# 7segement4digits1badidea-mk-4_1-smd.net
KiCad netlist of a schematic drawn in EAGLE
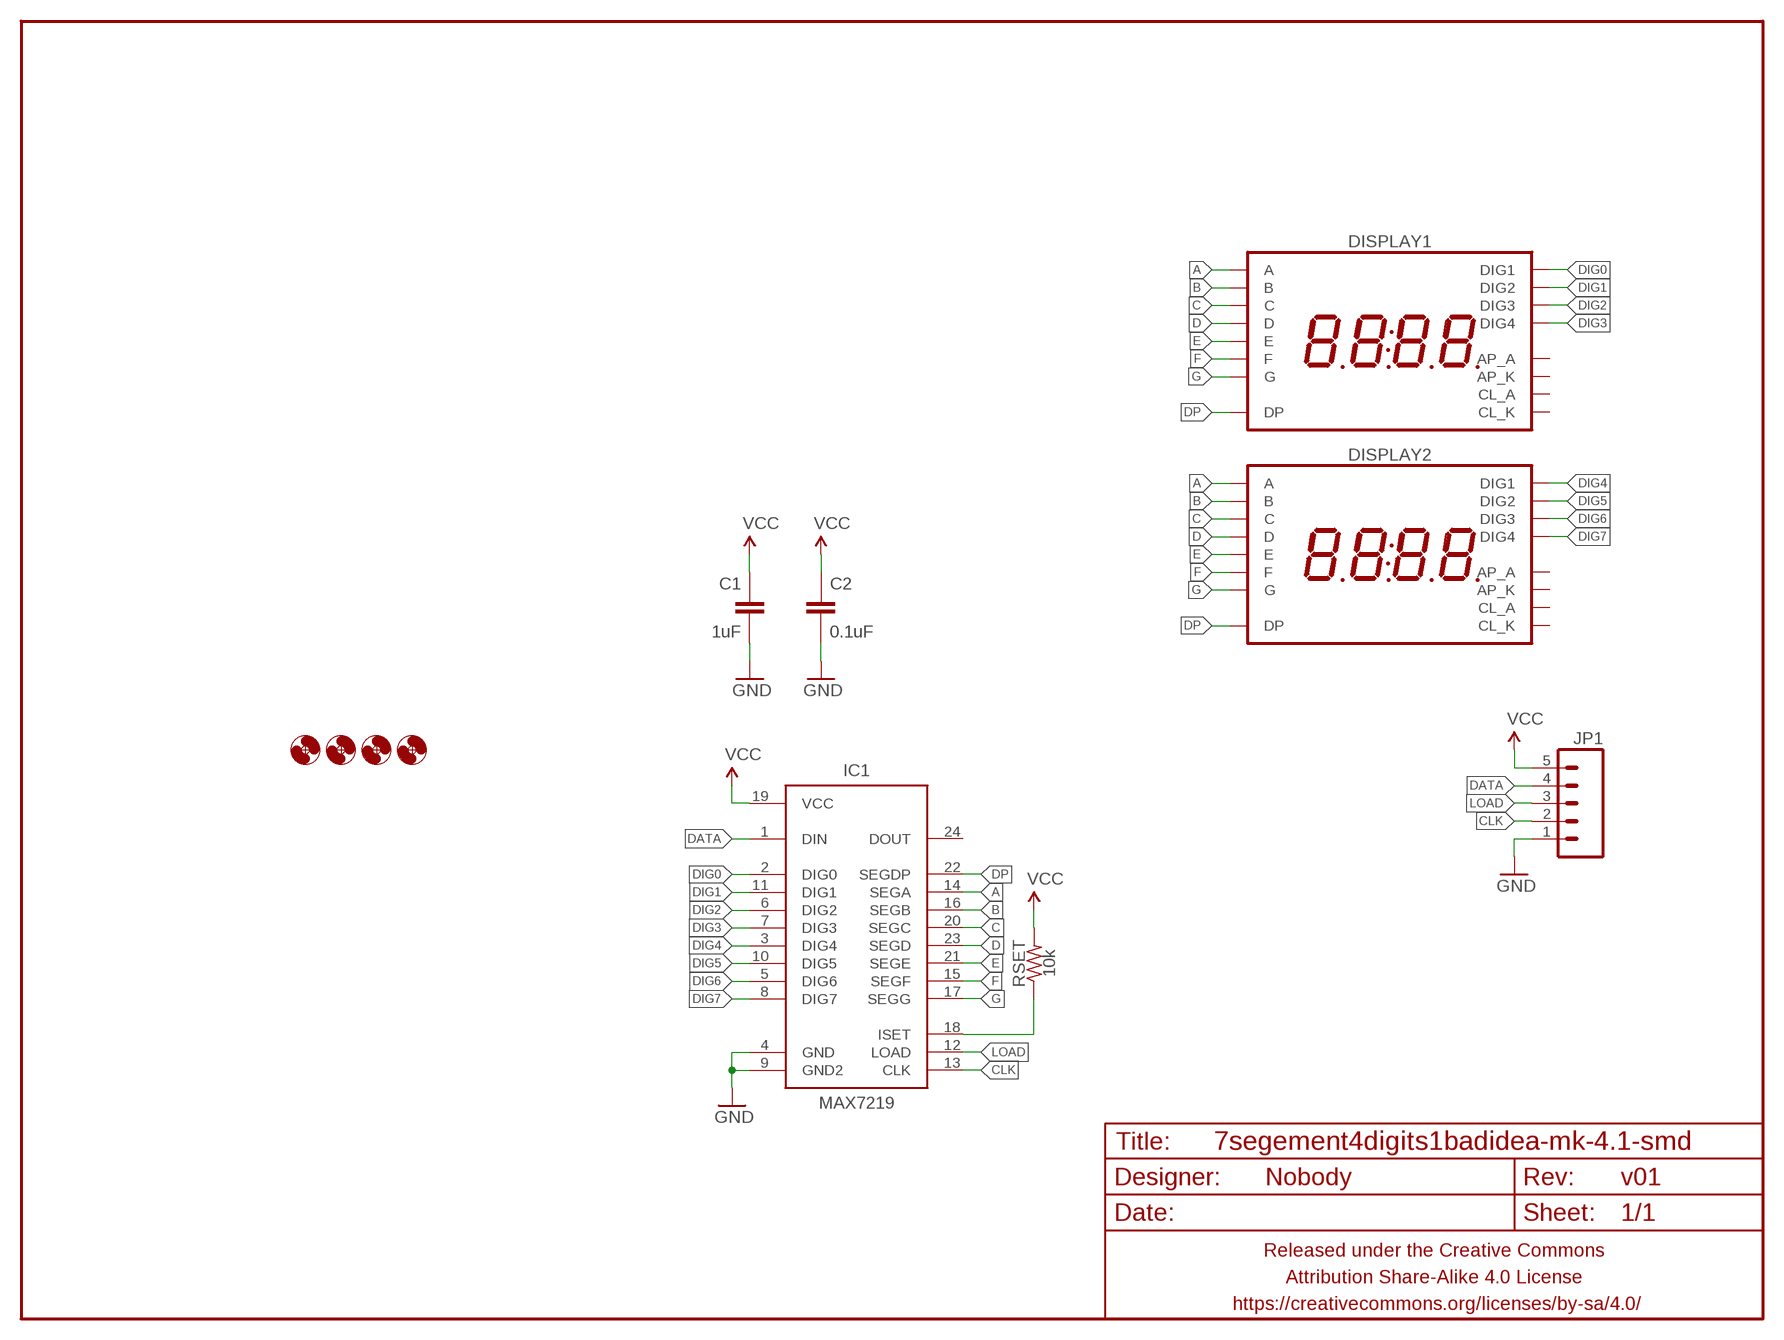
[diagram p0: schematic, sheet 1]

(export (version "E")
  (design (tool "Eeschema 10.0.6"))
  (components
    (comp (ref "C1")
      (value "1uF")
      (footprint "eagle-import:C025-024X044")
      (libsource (lib "eagle-import") (part "CAPACITOR-CERAMIC025-024X044"))
    )
    (comp (ref "C2")
      (value "0.1uF")
      (footprint "eagle-import:C025-024X044")
      (libsource (lib "eagle-import") (part "CAPACITOR-CERAMIC025-024X044"))
    )
    (comp (ref "DISPLAY1")
      (value "7SEG_4DIGIT_COLON_APOS")
      (footprint "eagle-import:7SEG_4DIG_10MM")
      (libsource (lib "eagle-import") (part "7SEG_4DIGIT_COLON_APOS"))
    )
    (comp (ref "DISPLAY2")
      (value "7SEG_4DIGIT_COLON_APOS")
      (footprint "eagle-import:7SEG_4DIG_10MM")
      (libsource (lib "eagle-import") (part "7SEG_4DIGIT_COLON_APOS"))
    )
    (comp (ref "FRAME1")
      (value "FRAME-LETTERNO_PACKAGE")
      (footprint "eagle-import:DUMMY")
      (fields (field (name "DESIGNER") "Nobody"))
      (libsource (lib "eagle-import") (part "FRAME-LETTERNO_PACKAGE"))
    )
    (comp (ref "H1")
      (value "HOLE#2")
      (footprint "eagle-import:HOLE-#2")
      (libsource (lib "eagle-import") (part "HOLE#2"))
    )
    (comp (ref "H2")
      (value "HOLE#2")
      (footprint "eagle-import:HOLE-#2")
      (libsource (lib "eagle-import") (part "HOLE#2"))
    )
    (comp (ref "H3")
      (value "HOLE#2")
      (footprint "eagle-import:HOLE-#2")
      (libsource (lib "eagle-import") (part "HOLE#2"))
    )
    (comp (ref "H4")
      (value "HOLE#2")
      (footprint "eagle-import:HOLE-#2")
      (libsource (lib "eagle-import") (part "HOLE#2"))
    )
    (comp (ref "IC1")
      (value "MAX7219")
      (footprint "eagle-import:SO24W")
      (libsource (lib "eagle-import") (part "MAX7219SOIC-W"))
    )
    (comp (ref "JP1")
      (value "M05PTH")
      (footprint "eagle-import:1X05")
      (libsource (lib "eagle-import") (part "M05PTH"))
    )
    (comp (ref "RSET")
      (value "10k")
      (footprint "eagle-import:RESISTOR-AXIAL-PTH-6.35MM")
      (libsource (lib "eagle-import") (part "RESISTORPTH-AXIAL-6.35MM"))
    )
  )
  (nets
    (net (code "1") (name "A") (class "Default")
      (node (ref "DISPLAY1") (pin "14") (pinfunction "A_14") (pintype "passive"))
      (node (ref "DISPLAY2") (pin "14") (pinfunction "A_14") (pintype "passive"))
      (node (ref "IC1") (pin "14") (pinfunction "SEGA_14") (pintype "bidirectional"))
    )
    (net (code "2") (name "B") (class "Default")
      (node (ref "DISPLAY1") (pin "16") (pinfunction "B_16") (pintype "passive"))
      (node (ref "DISPLAY2") (pin "16") (pinfunction "B_16") (pintype "passive"))
      (node (ref "IC1") (pin "16") (pinfunction "SEGB_16") (pintype "bidirectional"))
    )
    (net (code "3") (name "C") (class "Default")
      (node (ref "DISPLAY1") (pin "13") (pinfunction "C_13") (pintype "passive"))
      (node (ref "DISPLAY2") (pin "13") (pinfunction "C_13") (pintype "passive"))
      (node (ref "IC1") (pin "20") (pinfunction "SEGC_20") (pintype "bidirectional"))
    )
    (net (code "4") (name "CLK") (class "Default")
      (node (ref "IC1") (pin "13") (pinfunction "CLK_13") (pintype "bidirectional"))
      (node (ref "JP1") (pin "2") (pinfunction "2_2") (pintype "passive"))
    )
    (net (code "5") (name "D") (class "Default")
      (node (ref "DISPLAY1") (pin "3") (pinfunction "D_3") (pintype "passive"))
      (node (ref "DISPLAY2") (pin "3") (pinfunction "D_3") (pintype "passive"))
      (node (ref "IC1") (pin "23") (pinfunction "SEGD_23") (pintype "bidirectional"))
    )
    (net (code "6") (name "DATA") (class "Default")
      (node (ref "IC1") (pin "1") (pinfunction "DIN_1") (pintype "bidirectional"))
      (node (ref "JP1") (pin "4") (pinfunction "4_4") (pintype "passive"))
    )
    (net (code "7") (name "DIG0") (class "Default")
      (node (ref "DISPLAY1") (pin "1") (pinfunction "DIG1_1") (pintype "passive"))
      (node (ref "IC1") (pin "2") (pinfunction "DIG0_2") (pintype "bidirectional"))
    )
    (net (code "8") (name "DIG1") (class "Default")
      (node (ref "DISPLAY1") (pin "2") (pinfunction "DIG2_2") (pintype "passive"))
      (node (ref "IC1") (pin "11") (pinfunction "DIG1_11") (pintype "bidirectional"))
    )
    (net (code "9") (name "DIG2") (class "Default")
      (node (ref "DISPLAY1") (pin "6") (pinfunction "DIG3_6") (pintype "passive"))
      (node (ref "IC1") (pin "6") (pinfunction "DIG2_6") (pintype "bidirectional"))
    )
    (net (code "10") (name "DIG3") (class "Default")
      (node (ref "DISPLAY1") (pin "8") (pinfunction "DIG4_8") (pintype "passive"))
      (node (ref "IC1") (pin "7") (pinfunction "DIG3_7") (pintype "bidirectional"))
    )
    (net (code "11") (name "DIG4") (class "Default")
      (node (ref "DISPLAY2") (pin "1") (pinfunction "DIG1_1") (pintype "passive"))
      (node (ref "IC1") (pin "3") (pinfunction "DIG4_3") (pintype "bidirectional"))
    )
    (net (code "12") (name "DIG5") (class "Default")
      (node (ref "DISPLAY2") (pin "2") (pinfunction "DIG2_2") (pintype "passive"))
      (node (ref "IC1") (pin "10") (pinfunction "DIG5_10") (pintype "bidirectional"))
    )
    (net (code "13") (name "DIG6") (class "Default")
      (node (ref "DISPLAY2") (pin "6") (pinfunction "DIG3_6") (pintype "passive"))
      (node (ref "IC1") (pin "5") (pinfunction "DIG6_5") (pintype "bidirectional"))
    )
    (net (code "14") (name "DIG7") (class "Default")
      (node (ref "DISPLAY2") (pin "8") (pinfunction "DIG4_8") (pintype "passive"))
      (node (ref "IC1") (pin "8") (pinfunction "DIG7_8") (pintype "bidirectional"))
    )
    (net (code "15") (name "DP") (class "Default")
      (node (ref "DISPLAY1") (pin "7") (pinfunction "DP_7") (pintype "passive"))
      (node (ref "DISPLAY2") (pin "7") (pinfunction "DP_7") (pintype "passive"))
      (node (ref "IC1") (pin "22") (pinfunction "SEGDP_22") (pintype "bidirectional"))
    )
    (net (code "16") (name "E") (class "Default")
      (node (ref "DISPLAY1") (pin "5") (pinfunction "E_5") (pintype "passive"))
      (node (ref "DISPLAY2") (pin "5") (pinfunction "E_5") (pintype "passive"))
      (node (ref "IC1") (pin "21") (pinfunction "SEGE_21") (pintype "bidirectional"))
    )
    (net (code "17") (name "F") (class "Default")
      (node (ref "DISPLAY1") (pin "11") (pinfunction "F_11") (pintype "passive"))
      (node (ref "DISPLAY2") (pin "11") (pinfunction "F_11") (pintype "passive"))
      (node (ref "IC1") (pin "15") (pinfunction "SEGF_15") (pintype "bidirectional"))
    )
    (net (code "18") (name "G") (class "Default")
      (node (ref "DISPLAY1") (pin "15") (pinfunction "G_15") (pintype "passive"))
      (node (ref "DISPLAY2") (pin "15") (pinfunction "G_15") (pintype "passive"))
      (node (ref "IC1") (pin "17") (pinfunction "SEGG_17") (pintype "bidirectional"))
    )
    (net (code "19") (name "GND") (class "Default")
      (node (ref "C1") (pin "2") (pinfunction "2_2") (pintype "passive"))
      (node (ref "C2") (pin "2") (pinfunction "2_2") (pintype "passive"))
      (node (ref "IC1") (pin "4") (pinfunction "GND_4") (pintype "bidirectional"))
      (node (ref "IC1") (pin "9") (pinfunction "GND2_9") (pintype "bidirectional"))
      (node (ref "JP1") (pin "1") (pinfunction "1_1") (pintype "passive"))
    )
    (net (code "20") (name "LOAD") (class "Default")
      (node (ref "IC1") (pin "12") (pinfunction "LOAD_12") (pintype "bidirectional"))
      (node (ref "JP1") (pin "3") (pinfunction "3_3") (pintype "passive"))
    )
    (net (code "21") (name "Net-(IC1-ISET)") (class "Default")
      (node (ref "IC1") (pin "18") (pinfunction "ISET_18") (pintype "bidirectional"))
      (node (ref "RSET") (pin "P$1") (pinfunction "1_P$1") (pintype "passive"))
    )
    (net (code "22") (name "VCC") (class "Default")
      (node (ref "C1") (pin "1") (pinfunction "1_1") (pintype "passive"))
      (node (ref "C2") (pin "1") (pinfunction "1_1") (pintype "passive"))
      (node (ref "IC1") (pin "19") (pinfunction "VCC_19") (pintype "bidirectional"))
      (node (ref "JP1") (pin "5") (pinfunction "5_5") (pintype "passive"))
      (node (ref "RSET") (pin "P$2") (pinfunction "2_P$2") (pintype "passive"))
    )
    (net (code "23") (name "unconnected-(DISPLAY1-AP_A-Pad10)") (class "Default")
      (node (ref "DISPLAY1") (pin "10") (pinfunction "AP_A_10") (pintype "bidirectional"))
    )
    (net (code "24") (name "unconnected-(DISPLAY1-AP_K-Pad9)") (class "Default")
      (node (ref "DISPLAY1") (pin "9") (pinfunction "AP_K_9") (pintype "bidirectional"))
    )
    (net (code "25") (name "unconnected-(DISPLAY1-CL_A-Pad4)") (class "Default")
      (node (ref "DISPLAY1") (pin "4") (pinfunction "CL_A_4") (pintype "passive"))
    )
    (net (code "26") (name "unconnected-(DISPLAY1-CL_K-Pad12)") (class "Default")
      (node (ref "DISPLAY1") (pin "12") (pinfunction "CL_K_12") (pintype "passive"))
    )
    (net (code "27") (name "unconnected-(DISPLAY2-AP_A-Pad10)") (class "Default")
      (node (ref "DISPLAY2") (pin "10") (pinfunction "AP_A_10") (pintype "bidirectional"))
    )
    (net (code "28") (name "unconnected-(DISPLAY2-AP_K-Pad9)") (class "Default")
      (node (ref "DISPLAY2") (pin "9") (pinfunction "AP_K_9") (pintype "bidirectional"))
    )
    (net (code "29") (name "unconnected-(DISPLAY2-CL_A-Pad4)") (class "Default")
      (node (ref "DISPLAY2") (pin "4") (pinfunction "CL_A_4") (pintype "passive"))
    )
    (net (code "30") (name "unconnected-(DISPLAY2-CL_K-Pad12)") (class "Default")
      (node (ref "DISPLAY2") (pin "12") (pinfunction "CL_K_12") (pintype "passive"))
    )
    (net (code "31") (name "unconnected-(IC1-DOUT-Pad24)") (class "Default")
      (node (ref "IC1") (pin "24") (pinfunction "DOUT_24") (pintype "bidirectional"))
    )
  )
)
